# glowna.net
KiCad netlist of a schematic drawn in EAGLE
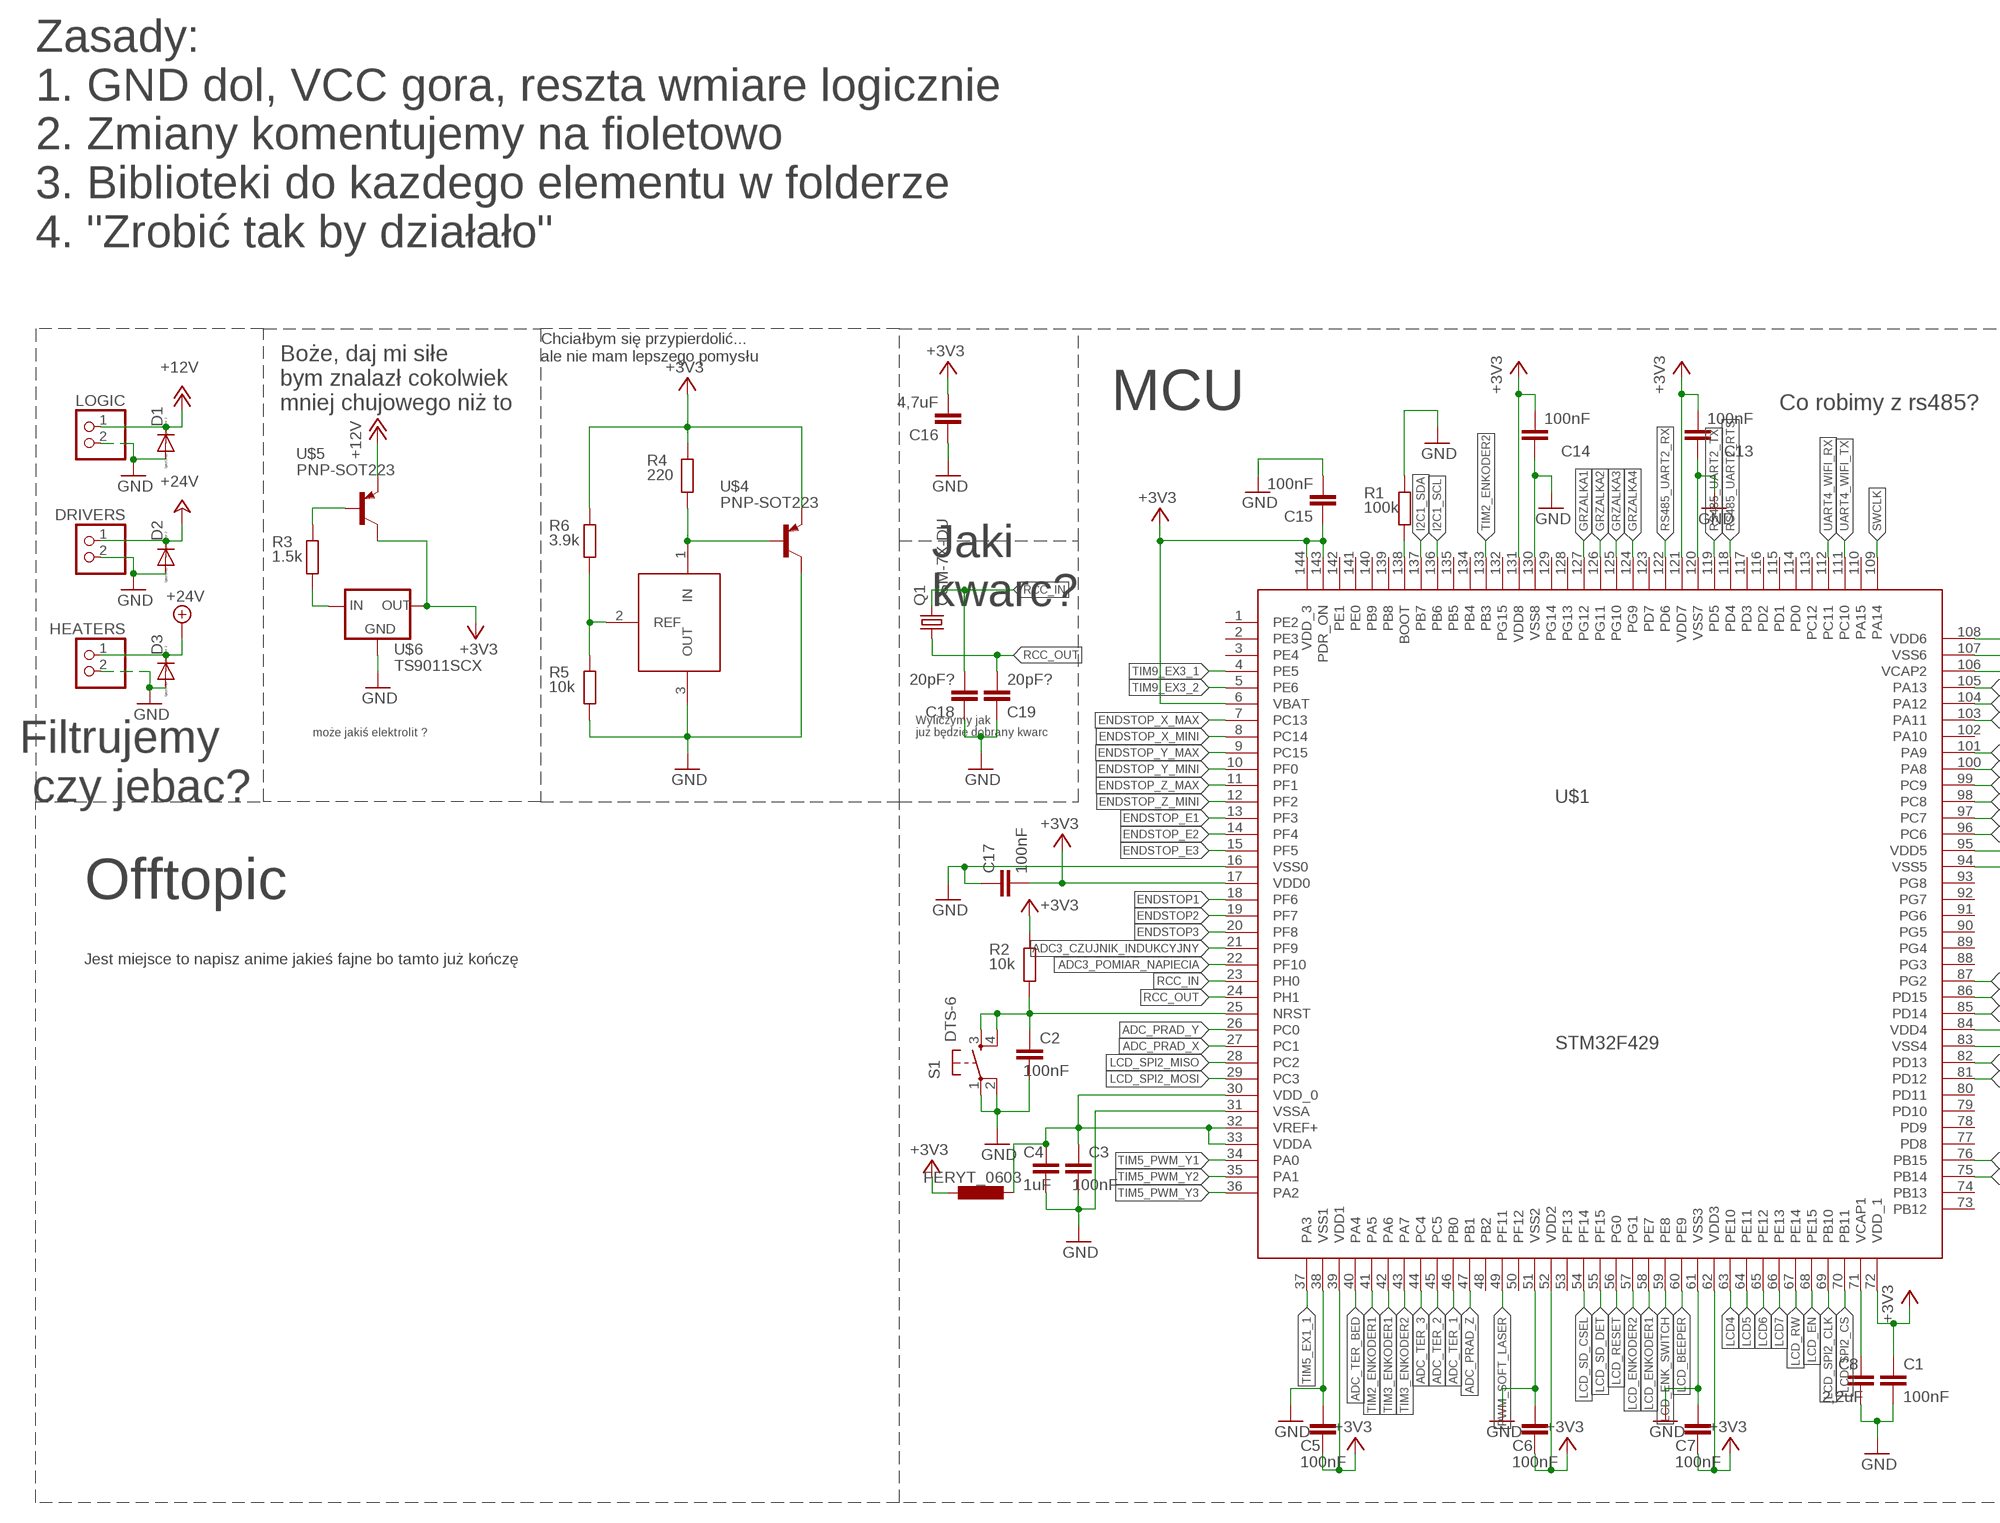
[diagram p0: schematic, sheet 1, part 1 of 2]
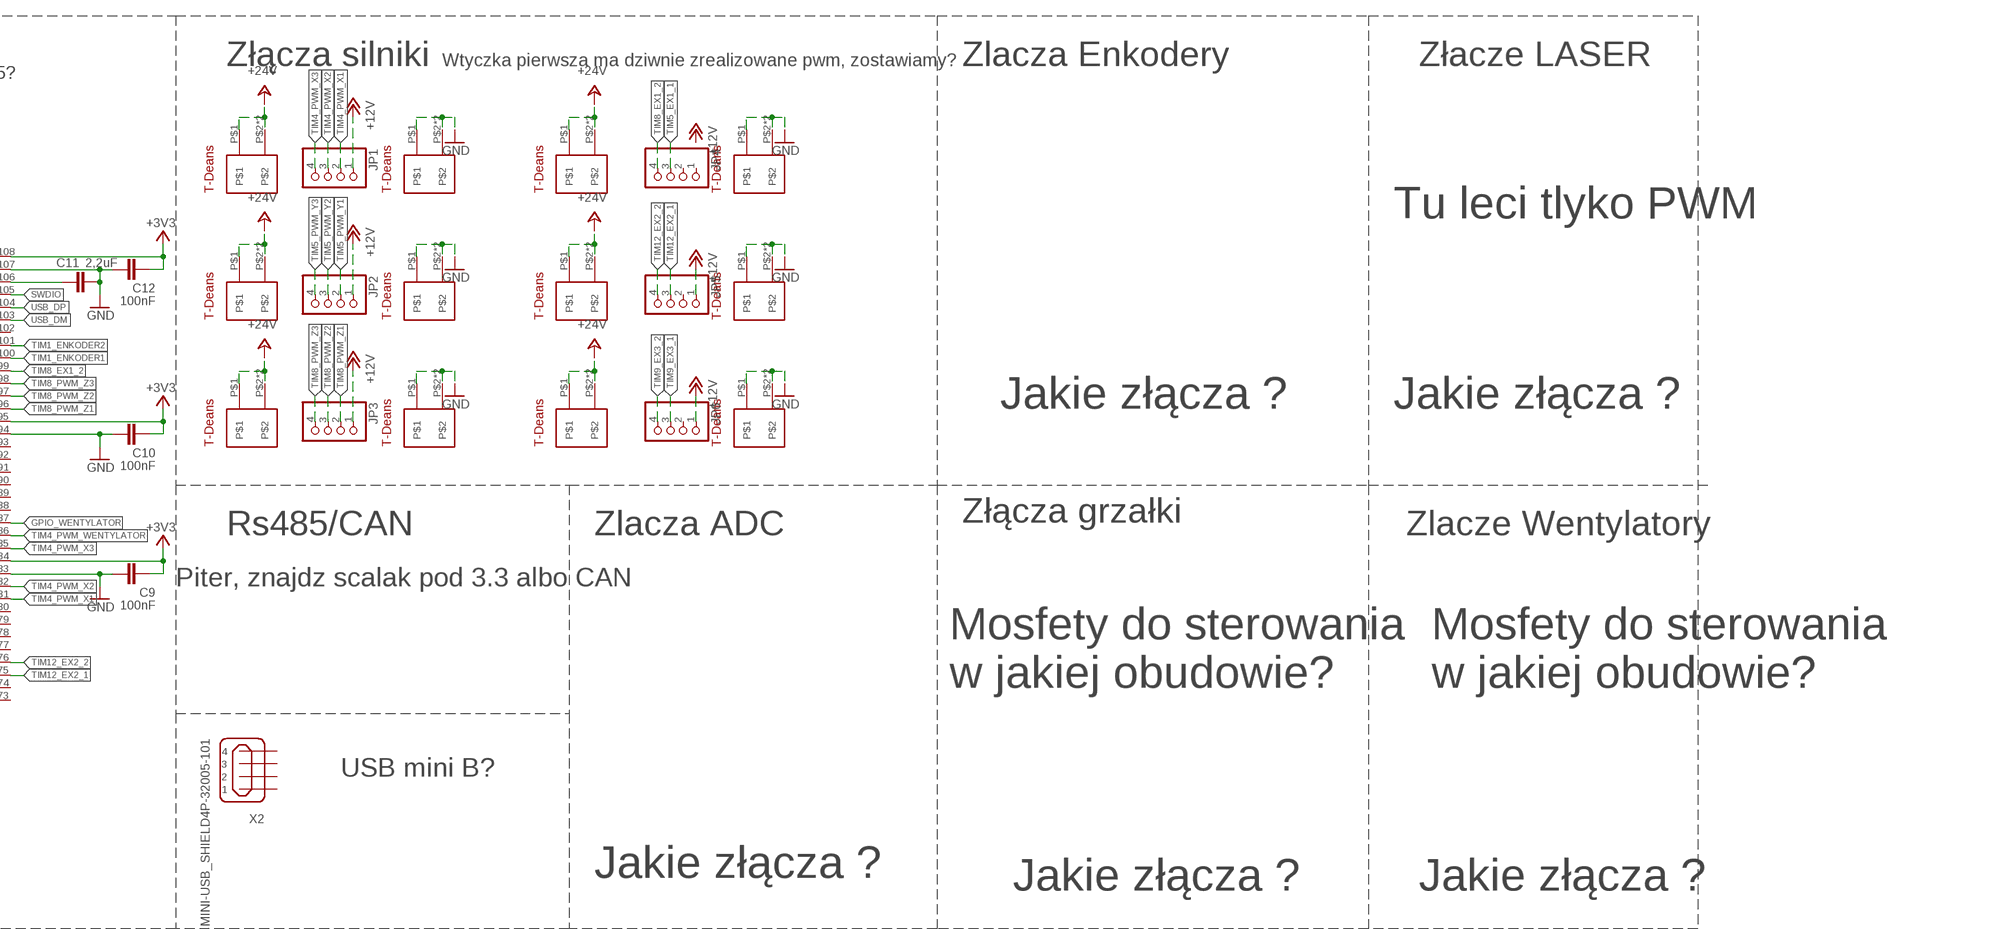
[diagram p1: schematic, sheet 1, part 2 of 2]

(export (version "E")
  (design (tool "Eeschema 10.0.6"))
  (components
    (comp (ref "C1")
      (value "100nF")
      (footprint "eagle-import:C0603")
      (libsource (lib "eagle-import") (part "C-EUC0603"))
    )
    (comp (ref "C2")
      (value "100nF")
      (footprint "eagle-import:C0603")
      (libsource (lib "eagle-import") (part "C-EUC0603"))
    )
    (comp (ref "C3")
      (value "100nF")
      (footprint "eagle-import:C0603")
      (libsource (lib "eagle-import") (part "C-EUC0603"))
    )
    (comp (ref "C4")
      (value "1uF")
      (footprint "eagle-import:C0603")
      (libsource (lib "eagle-import") (part "C-EUC0603"))
    )
    (comp (ref "C5")
      (value "100nF")
      (footprint "eagle-import:C0603")
      (libsource (lib "eagle-import") (part "C-EUC0603"))
    )
    (comp (ref "C6")
      (value "100nF")
      (footprint "eagle-import:C0603")
      (libsource (lib "eagle-import") (part "C-EUC0603"))
    )
    (comp (ref "C7")
      (value "100nF")
      (footprint "eagle-import:C0603")
      (libsource (lib "eagle-import") (part "C-EUC0603"))
    )
    (comp (ref "C8")
      (value "2,2uF")
      (footprint "eagle-import:C0603")
      (libsource (lib "eagle-import") (part "C-EUC0603"))
    )
    (comp (ref "C9")
      (value "100nF")
      (footprint "eagle-import:C0603")
      (libsource (lib "eagle-import") (part "C-EUC0603"))
    )
    (comp (ref "C10")
      (value "100nF")
      (footprint "eagle-import:C0603")
      (libsource (lib "eagle-import") (part "C-EUC0603"))
    )
    (comp (ref "C11")
      (value "2,2uF")
      (footprint "eagle-import:C0603")
      (libsource (lib "eagle-import") (part "C-EUC0603"))
    )
    (comp (ref "C12")
      (value "100nF")
      (footprint "eagle-import:C0603")
      (libsource (lib "eagle-import") (part "C-EUC0603"))
    )
    (comp (ref "C13")
      (value "100nF")
      (footprint "eagle-import:C0603")
      (libsource (lib "eagle-import") (part "C-EUC0603"))
    )
    (comp (ref "C14")
      (value "100nF")
      (footprint "eagle-import:C0603")
      (libsource (lib "eagle-import") (part "C-EUC0603"))
    )
    (comp (ref "C15")
      (value "100nF")
      (footprint "eagle-import:C0603")
      (libsource (lib "eagle-import") (part "C-EUC0603"))
    )
    (comp (ref "C16")
      (value "4,7uF")
      (footprint "eagle-import:C0603")
      (libsource (lib "eagle-import") (part "C-EUC0603"))
    )
    (comp (ref "C17")
      (value "100nF")
      (footprint "eagle-import:C0603")
      (libsource (lib "eagle-import") (part "C-EUC0603"))
    )
    (comp (ref "C18")
      (value "20pF?")
      (footprint "eagle-import:C0603")
      (libsource (lib "eagle-import") (part "C-EUC0603"))
    )
    (comp (ref "C19")
      (value "20pF?")
      (footprint "eagle-import:C0603")
      (libsource (lib "eagle-import") (part "C-EUC0603"))
    )
    (comp (ref "D1")
      (value "DIODE-DO-214AC")
      (footprint "eagle-import:DO-214AC")
      (libsource (lib "eagle-import") (part "DIODE-DO-214AC"))
    )
    (comp (ref "D2")
      (value "DIODE-DO-214AC")
      (footprint "eagle-import:DO-214AC")
      (libsource (lib "eagle-import") (part "DIODE-DO-214AC"))
    )
    (comp (ref "D3")
      (value "DIODE-DO-214AC")
      (footprint "eagle-import:DO-214AC")
      (libsource (lib "eagle-import") (part "DIODE-DO-214AC"))
    )
    (comp (ref "DRIVERS")
      (value "PINHD-1X2")
      (footprint "eagle-import:1X02")
      (libsource (lib "eagle-import") (part "PINHD-1X2"))
    )
    (comp (ref "HEATERS")
      (value "PINHD-1X2")
      (footprint "eagle-import:1X02")
      (libsource (lib "eagle-import") (part "PINHD-1X2"))
    )
    (comp (ref "JP1")
      (value "PINHD-1X4")
      (footprint "eagle-import:1X04")
      (libsource (lib "eagle-import") (part "PINHD-1X4"))
    )
    (comp (ref "JP2")
      (value "PINHD-1X4")
      (footprint "eagle-import:1X04")
      (libsource (lib "eagle-import") (part "PINHD-1X4"))
    )
    (comp (ref "JP3")
      (value "PINHD-1X4")
      (footprint "eagle-import:1X04")
      (libsource (lib "eagle-import") (part "PINHD-1X4"))
    )
    (comp (ref "JP4")
      (value "PINHD-1X4")
      (footprint "eagle-import:1X04")
      (libsource (lib "eagle-import") (part "PINHD-1X4"))
    )
    (comp (ref "JP5")
      (value "PINHD-1X4")
      (footprint "eagle-import:1X04")
      (libsource (lib "eagle-import") (part "PINHD-1X4"))
    )
    (comp (ref "JP6")
      (value "PINHD-1X4")
      (footprint "eagle-import:1X04")
      (libsource (lib "eagle-import") (part "PINHD-1X4"))
    )
    (comp (ref "LOGIC")
      (value "PINHD-1X2")
      (footprint "eagle-import:1X02")
      (libsource (lib "eagle-import") (part "PINHD-1X2"))
    )
    (comp (ref "Q1")
      (value "CSM-7X-DU")
      (footprint "eagle-import:CSM-7X-DU")
      (libsource (lib "eagle-import") (part "CSM-7X-DU"))
    )
    (comp (ref "R1")
      (value "100k")
      (footprint "eagle-import:R0603")
      (libsource (lib "eagle-import") (part "R-EU_R0603"))
    )
    (comp (ref "R2")
      (value "10k")
      (footprint "eagle-import:R0603")
      (libsource (lib "eagle-import") (part "R-EU_R0603"))
    )
    (comp (ref "R3")
      (value "1.5k")
      (footprint "eagle-import:R0603")
      (libsource (lib "eagle-import") (part "R-EU_R0603"))
    )
    (comp (ref "R4")
      (value "220")
      (footprint "eagle-import:R0603")
      (libsource (lib "eagle-import") (part "R-EU_R0603"))
    )
    (comp (ref "R5")
      (value "10k")
      (footprint "eagle-import:R0603")
      (libsource (lib "eagle-import") (part "R-EU_R0603"))
    )
    (comp (ref "R6")
      (value "3.9k")
      (footprint "eagle-import:R0603")
      (libsource (lib "eagle-import") (part "R-EU_R0603"))
    )
    (comp (ref "S1")
      (value "DTS-6")
      (footprint "eagle-import:DTS-6")
      (libsource (lib "eagle-import") (part "DTS-6"))
    )
    (comp (ref "U$1")
      (value "STM32F429")
      (footprint "eagle-import:SQFP-S-20X20-144")
      (libsource (lib "eagle-import") (part "STM32F429"))
    )
    (comp (ref "U$2")
      (value "FERYT_0603")
      (footprint "eagle-import:R0603")
      (libsource (lib "eagle-import") (part "FERYT_0603"))
    )
    (comp (ref "U$3")
      (value "TL431AIDBZR")
      (footprint "eagle-import:SOT23")
      (libsource (lib "eagle-import") (part "TL431AIDBZR"))
    )
    (comp (ref "U$4")
      (value "PNP-SOT223")
      (footprint "eagle-import:SOT223")
      (libsource (lib "eagle-import") (part "PNP-SOT223"))
    )
    (comp (ref "U$5")
      (value "PNP-SOT223")
      (footprint "eagle-import:SOT223")
      (libsource (lib "eagle-import") (part "PNP-SOT223"))
    )
    (comp (ref "U$6")
      (value "TS9011SCX")
      (footprint "eagle-import:SOT23")
      (libsource (lib "eagle-import") (part "TS9011SCX"))
    )
    (comp (ref "U$7")
      (value "T-DEANS")
      (footprint "eagle-import:T-DEANS")
      (libsource (lib "eagle-import") (part "T-DEANS"))
    )
    (comp (ref "U$8")
      (value "T-DEANS")
      (footprint "eagle-import:T-DEANS")
      (libsource (lib "eagle-import") (part "T-DEANS"))
    )
    (comp (ref "U$9")
      (value "T-DEANS")
      (footprint "eagle-import:T-DEANS")
      (libsource (lib "eagle-import") (part "T-DEANS"))
    )
    (comp (ref "U$10")
      (value "T-DEANS")
      (footprint "eagle-import:T-DEANS")
      (libsource (lib "eagle-import") (part "T-DEANS"))
    )
    (comp (ref "U$11")
      (value "T-DEANS")
      (footprint "eagle-import:T-DEANS")
      (libsource (lib "eagle-import") (part "T-DEANS"))
    )
    (comp (ref "U$12")
      (value "T-DEANS")
      (footprint "eagle-import:T-DEANS")
      (libsource (lib "eagle-import") (part "T-DEANS"))
    )
    (comp (ref "U$13")
      (value "T-DEANS")
      (footprint "eagle-import:T-DEANS")
      (libsource (lib "eagle-import") (part "T-DEANS"))
    )
    (comp (ref "U$14")
      (value "T-DEANS")
      (footprint "eagle-import:T-DEANS")
      (libsource (lib "eagle-import") (part "T-DEANS"))
    )
    (comp (ref "U$15")
      (value "T-DEANS")
      (footprint "eagle-import:T-DEANS")
      (libsource (lib "eagle-import") (part "T-DEANS"))
    )
    (comp (ref "U$16")
      (value "T-DEANS")
      (footprint "eagle-import:T-DEANS")
      (libsource (lib "eagle-import") (part "T-DEANS"))
    )
    (comp (ref "U$17")
      (value "T-DEANS")
      (footprint "eagle-import:T-DEANS")
      (libsource (lib "eagle-import") (part "T-DEANS"))
    )
    (comp (ref "U$18")
      (value "T-DEANS")
      (footprint "eagle-import:T-DEANS")
      (libsource (lib "eagle-import") (part "T-DEANS"))
    )
    (comp (ref "X2")
      (value "MINI-USB_SHIELD4P-32005-101")
      (footprint "eagle-import:32005-101")
      (libsource (lib "eagle-import") (part "MINI-USB_SHIELD4P-32005-101"))
    )
  )
  (nets
    (net (code "1") (name "+3V3") (class "Default")
      (node (ref "C1") (pin "1") (pinfunction "1_1") (pintype "passive"))
      (node (ref "C10") (pin "2") (pinfunction "2_2") (pintype "passive"))
      (node (ref "C12") (pin "2") (pinfunction "2_2") (pintype "passive"))
      (node (ref "C13") (pin "2") (pinfunction "2_2") (pintype "passive"))
      (node (ref "C14") (pin "2") (pinfunction "2_2") (pintype "passive"))
      (node (ref "C15") (pin "1") (pinfunction "1_1") (pintype "passive"))
      (node (ref "C16") (pin "2") (pinfunction "2_2") (pintype "passive"))
      (node (ref "C17") (pin "2") (pinfunction "2_2") (pintype "passive"))
      (node (ref "C5") (pin "2") (pinfunction "2_2") (pintype "passive"))
      (node (ref "C6") (pin "2") (pinfunction "2_2") (pintype "passive"))
      (node (ref "C7") (pin "2") (pinfunction "2_2") (pintype "passive"))
      (node (ref "C9") (pin "2") (pinfunction "2_2") (pintype "passive"))
      (node (ref "R2") (pin "1") (pinfunction "1_1") (pintype "passive"))
      (node (ref "R4") (pin "1") (pinfunction "1_1") (pintype "passive"))
      (node (ref "R6") (pin "1") (pinfunction "1_1") (pintype "passive"))
      (node (ref "U$1") (pin "108") (pinfunction "VDD6_108") (pintype "bidirectional"))
      (node (ref "U$1") (pin "121") (pinfunction "VDD7_121") (pintype "bidirectional"))
      (node (ref "U$1") (pin "131") (pinfunction "VDD8_131") (pintype "bidirectional"))
      (node (ref "U$1") (pin "143") (pinfunction "PDR_ON_143") (pintype "bidirectional"))
      (node (ref "U$1") (pin "144") (pinfunction "VDD_3_144") (pintype "bidirectional"))
      (node (ref "U$1") (pin "17") (pinfunction "VDD0_17") (pintype "bidirectional"))
      (node (ref "U$1") (pin "39") (pinfunction "VDD1_39") (pintype "bidirectional"))
      (node (ref "U$1") (pin "52") (pinfunction "VDD2_52") (pintype "bidirectional"))
      (node (ref "U$1") (pin "6") (pinfunction "VBAT_6") (pintype "bidirectional"))
      (node (ref "U$1") (pin "62") (pinfunction "VDD3_62") (pintype "bidirectional"))
      (node (ref "U$1") (pin "72") (pinfunction "VDD_1_72") (pintype "bidirectional"))
      (node (ref "U$1") (pin "84") (pinfunction "VDD4_84") (pintype "bidirectional"))
      (node (ref "U$1") (pin "95") (pinfunction "VDD5_95") (pintype "bidirectional"))
      (node (ref "U$2") (pin "1") (pinfunction "1_1") (pintype "passive"))
      (node (ref "U$4") (pin "3") (pinfunction "E_3") (pintype "passive"))
      (node (ref "U$5") (pin "2") (pinfunction "C_2") (pintype "passive"))
      (node (ref "U$5") (pin "4") (pinfunction "C_4") (pintype "passive"))
      (node (ref "U$6") (pin "2") (pinfunction "OUT_2") (pintype "passive"))
    )
    (net (code "2") (name "+12V") (class "Default")
      (node (ref "D1") (pin "C") (pinfunction "C_C") (pintype "passive"))
      (node (ref "JP1") (pin "1") (pinfunction "1_1") (pintype "passive"))
      (node (ref "JP2") (pin "1") (pinfunction "1_1") (pintype "passive"))
      (node (ref "JP3") (pin "1") (pinfunction "1_1") (pintype "passive"))
      (node (ref "JP5") (pin "1") (pinfunction "1_1") (pintype "passive"))
      (node (ref "JP6") (pin "1") (pinfunction "1_1") (pintype "passive"))
      (node (ref "LOGIC") (pin "1") (pinfunction "1_1") (pintype "passive"))
      (node (ref "U$5") (pin "3") (pinfunction "E_3") (pintype "passive"))
    )
    (net (code "3") (name "+24V") (class "Default")
      (node (ref "D2") (pin "C") (pinfunction "C_C") (pintype "passive"))
      (node (ref "D3") (pin "C") (pinfunction "C_C") (pintype "passive"))
      (node (ref "DRIVERS") (pin "1") (pinfunction "1_1") (pintype "passive"))
      (node (ref "HEATERS") (pin "1") (pinfunction "1_1") (pintype "passive"))
      (node (ref "U$11") (pin "P$1") (pinfunction "P$1_P$1") (pintype "bidirectional"))
      (node (ref "U$11") (pin "P$2") (pinfunction "P$2_P$2") (pintype "bidirectional"))
      (node (ref "U$11") (pin "P$3") (pinfunction "P$2_P$3") (pintype "bidirectional"))
      (node (ref "U$13") (pin "P$1") (pinfunction "P$1_P$1") (pintype "bidirectional"))
      (node (ref "U$13") (pin "P$2") (pinfunction "P$2_P$2") (pintype "bidirectional"))
      (node (ref "U$13") (pin "P$3") (pinfunction "P$2_P$3") (pintype "bidirectional"))
      (node (ref "U$15") (pin "P$1") (pinfunction "P$1_P$1") (pintype "bidirectional"))
      (node (ref "U$15") (pin "P$2") (pinfunction "P$2_P$2") (pintype "bidirectional"))
      (node (ref "U$15") (pin "P$3") (pinfunction "P$2_P$3") (pintype "bidirectional"))
      (node (ref "U$17") (pin "P$1") (pinfunction "P$1_P$1") (pintype "bidirectional"))
      (node (ref "U$17") (pin "P$2") (pinfunction "P$2_P$2") (pintype "bidirectional"))
      (node (ref "U$17") (pin "P$3") (pinfunction "P$2_P$3") (pintype "bidirectional"))
      (node (ref "U$7") (pin "P$1") (pinfunction "P$1_P$1") (pintype "bidirectional"))
      (node (ref "U$7") (pin "P$2") (pinfunction "P$2_P$2") (pintype "bidirectional"))
      (node (ref "U$7") (pin "P$3") (pinfunction "P$2_P$3") (pintype "bidirectional"))
      (node (ref "U$9") (pin "P$1") (pinfunction "P$1_P$1") (pintype "bidirectional"))
      (node (ref "U$9") (pin "P$2") (pinfunction "P$2_P$2") (pintype "bidirectional"))
      (node (ref "U$9") (pin "P$3") (pinfunction "P$2_P$3") (pintype "bidirectional"))
    )
    (net (code "4") (name "ADC3_CZUJNIK_INDUKCYJNY") (class "Default")
      (node (ref "U$1") (pin "21") (pinfunction "PF9_21") (pintype "bidirectional"))
    )
    (net (code "5") (name "ADC3_POMIAR_NAPIECIA") (class "Default")
      (node (ref "U$1") (pin "22") (pinfunction "PF10_22") (pintype "bidirectional"))
    )
    (net (code "6") (name "ADC_PRAD_X") (class "Default")
      (node (ref "U$1") (pin "27") (pinfunction "PC1_27") (pintype "bidirectional"))
    )
    (net (code "7") (name "ADC_PRAD_Y") (class "Default")
      (node (ref "U$1") (pin "26") (pinfunction "PC0_26") (pintype "bidirectional"))
    )
    (net (code "8") (name "ADC_PRAD_Z") (class "Default")
      (node (ref "U$1") (pin "47") (pinfunction "PB1_47") (pintype "bidirectional"))
    )
    (net (code "9") (name "ADC_TER_1") (class "Default")
      (node (ref "U$1") (pin "46") (pinfunction "PB0_46") (pintype "bidirectional"))
    )
    (net (code "10") (name "ADC_TER_2") (class "Default")
      (node (ref "U$1") (pin "45") (pinfunction "PC5_45") (pintype "bidirectional"))
    )
    (net (code "11") (name "ADC_TER_3") (class "Default")
      (node (ref "U$1") (pin "44") (pinfunction "PC4_44") (pintype "bidirectional"))
    )
    (net (code "12") (name "ADC_TER_BED") (class "Default")
      (node (ref "U$1") (pin "40") (pinfunction "PA4_40") (pintype "bidirectional"))
    )
    (net (code "13") (name "ENDSTOP1") (class "Default")
      (node (ref "U$1") (pin "18") (pinfunction "PF6_18") (pintype "bidirectional"))
    )
    (net (code "14") (name "ENDSTOP2") (class "Default")
      (node (ref "U$1") (pin "19") (pinfunction "PF7_19") (pintype "bidirectional"))
    )
    (net (code "15") (name "ENDSTOP3") (class "Default")
      (node (ref "U$1") (pin "20") (pinfunction "PF8_20") (pintype "bidirectional"))
    )
    (net (code "16") (name "ENDSTOP_E1") (class "Default")
      (node (ref "U$1") (pin "13") (pinfunction "PF3_13") (pintype "bidirectional"))
    )
    (net (code "17") (name "ENDSTOP_E2") (class "Default")
      (node (ref "U$1") (pin "14") (pinfunction "PF4_14") (pintype "bidirectional"))
    )
    (net (code "18") (name "ENDSTOP_E3") (class "Default")
      (node (ref "U$1") (pin "15") (pinfunction "PF5_15") (pintype "bidirectional"))
    )
    (net (code "19") (name "ENDSTOP_X_MAX") (class "Default")
      (node (ref "U$1") (pin "7") (pinfunction "PC13_7") (pintype "bidirectional"))
    )
    (net (code "20") (name "ENDSTOP_X_MINI") (class "Default")
      (node (ref "U$1") (pin "8") (pinfunction "PC14_8") (pintype "bidirectional"))
    )
    (net (code "21") (name "ENDSTOP_Y_MAX") (class "Default")
      (node (ref "U$1") (pin "9") (pinfunction "PC15_9") (pintype "bidirectional"))
    )
    (net (code "22") (name "ENDSTOP_Y_MINI") (class "Default")
      (node (ref "U$1") (pin "10") (pinfunction "PF0_10") (pintype "bidirectional"))
    )
    (net (code "23") (name "ENDSTOP_Z_MAX") (class "Default")
      (node (ref "U$1") (pin "11") (pinfunction "PF1_11") (pintype "bidirectional"))
    )
    (net (code "24") (name "ENDSTOP_Z_MINI") (class "Default")
      (node (ref "U$1") (pin "12") (pinfunction "PF2_12") (pintype "bidirectional"))
    )
    (net (code "25") (name "GND") (class "Default")
      (node (ref "C1") (pin "2") (pinfunction "2_2") (pintype "passive"))
      (node (ref "C10") (pin "1") (pinfunction "1_1") (pintype "passive"))
      (node (ref "C11") (pin "2") (pinfunction "2_2") (pintype "passive"))
      (node (ref "C12") (pin "1") (pinfunction "1_1") (pintype "passive"))
      (node (ref "C13") (pin "1") (pinfunction "1_1") (pintype "passive"))
      (node (ref "C14") (pin "1") (pinfunction "1_1") (pintype "passive"))
      (node (ref "C15") (pin "2") (pinfunction "2_2") (pintype "passive"))
      (node (ref "C16") (pin "1") (pinfunction "1_1") (pintype "passive"))
      (node (ref "C17") (pin "1") (pinfunction "1_1") (pintype "passive"))
      (node (ref "C18") (pin "1") (pinfunction "1_1") (pintype "passive"))
      (node (ref "C19") (pin "1") (pinfunction "1_1") (pintype "passive"))
      (node (ref "C2") (pin "2") (pinfunction "2_2") (pintype "passive"))
      (node (ref "C3") (pin "2") (pinfunction "2_2") (pintype "passive"))
      (node (ref "C4") (pin "2") (pinfunction "2_2") (pintype "passive"))
      (node (ref "C5") (pin "1") (pinfunction "1_1") (pintype "passive"))
      (node (ref "C6") (pin "1") (pinfunction "1_1") (pintype "passive"))
      (node (ref "C7") (pin "1") (pinfunction "1_1") (pintype "passive"))
      (node (ref "C8") (pin "2") (pinfunction "2_2") (pintype "passive"))
      (node (ref "C9") (pin "1") (pinfunction "1_1") (pintype "passive"))
      (node (ref "D1") (pin "A") (pinfunction "A_A") (pintype "passive"))
      (node (ref "D2") (pin "A") (pinfunction "A_A") (pintype "passive"))
      (node (ref "D3") (pin "A") (pinfunction "A_A") (pintype "passive"))
      (node (ref "DRIVERS") (pin "2") (pinfunction "2_2") (pintype "passive"))
      (node (ref "HEATERS") (pin "2") (pinfunction "2_2") (pintype "passive"))
      (node (ref "LOGIC") (pin "2") (pinfunction "2_2") (pintype "passive"))
      (node (ref "R1") (pin "1") (pinfunction "1_1") (pintype "passive"))
      (node (ref "R5") (pin "2") (pinfunction "2_2") (pintype "passive"))
      (node (ref "S1") (pin "1") (pinfunction "1_1") (pintype "passive"))
      (node (ref "S1") (pin "2") (pinfunction "2_2") (pintype "passive"))
      (node (ref "U$1") (pin "107") (pinfunction "VSS6_107") (pintype "bidirectional"))
      (node (ref "U$1") (pin "120") (pinfunction "VSS7_120") (pintype "bidirectional"))
      (node (ref "U$1") (pin "130") (pinfunction "VSS8_130") (pintype "bidirectional"))
      (node (ref "U$1") (pin "16") (pinfunction "VSS0_16") (pintype "bidirectional"))
      (node (ref "U$1") (pin "31") (pinfunction "VSSA_31") (pintype "bidirectional"))
      (node (ref "U$1") (pin "38") (pinfunction "VSS1_38") (pintype "bidirectional"))
      (node (ref "U$1") (pin "51") (pinfunction "VSS2_51") (pintype "bidirectional"))
      (node (ref "U$1") (pin "61") (pinfunction "VSS3_61") (pintype "bidirectional"))
      (node (ref "U$1") (pin "83") (pinfunction "VSS4_83") (pintype "bidirectional"))
      (node (ref "U$1") (pin "94") (pinfunction "VSS5_94") (pintype "bidirectional"))
      (node (ref "U$10") (pin "P$1") (pinfunction "P$1_P$1") (pintype "bidirectional"))
      (node (ref "U$10") (pin "P$2") (pinfunction "P$2_P$2") (pintype "bidirectional"))
      (node (ref "U$10") (pin "P$3") (pinfunction "P$2_P$3") (pintype "bidirectional"))
      (node (ref "U$12") (pin "P$1") (pinfunction "P$1_P$1") (pintype "bidirectional"))
      (node (ref "U$12") (pin "P$2") (pinfunction "P$2_P$2") (pintype "bidirectional"))
      (node (ref "U$12") (pin "P$3") (pinfunction "P$2_P$3") (pintype "bidirectional"))
      (node (ref "U$14") (pin "P$1") (pinfunction "P$1_P$1") (pintype "bidirectional"))
      (node (ref "U$14") (pin "P$2") (pinfunction "P$2_P$2") (pintype "bidirectional"))
      (node (ref "U$14") (pin "P$3") (pinfunction "P$2_P$3") (pintype "bidirectional"))
      (node (ref "U$16") (pin "P$1") (pinfunction "P$1_P$1") (pintype "bidirectional"))
      (node (ref "U$16") (pin "P$2") (pinfunction "P$2_P$2") (pintype "bidirectional"))
      (node (ref "U$16") (pin "P$3") (pinfunction "P$2_P$3") (pintype "bidirectional"))
      (node (ref "U$18") (pin "P$1") (pinfunction "P$1_P$1") (pintype "bidirectional"))
      (node (ref "U$18") (pin "P$2") (pinfunction "P$2_P$2") (pintype "bidirectional"))
      (node (ref "U$18") (pin "P$3") (pinfunction "P$2_P$3") (pintype "bidirectional"))
      (node (ref "U$3") (pin "3") (pinfunction "OUT_3") (pintype "bidirectional"))
      (node (ref "U$4") (pin "2") (pinfunction "C_2") (pintype "passive"))
      (node (ref "U$4") (pin "4") (pinfunction "C_4") (pintype "passive"))
      (node (ref "U$6") (pin "1") (pinfunction "GND_1") (pintype "input"))
      (node (ref "U$8") (pin "P$1") (pinfunction "P$1_P$1") (pintype "bidirectional"))
      (node (ref "U$8") (pin "P$2") (pinfunction "P$2_P$2") (pintype "bidirectional"))
      (node (ref "U$8") (pin "P$3") (pinfunction "P$2_P$3") (pintype "bidirectional"))
    )
    (net (code "26") (name "GPIO_WENTYLATOR") (class "Default")
      (node (ref "U$1") (pin "87") (pinfunction "PG2_87") (pintype "bidirectional"))
    )
    (net (code "27") (name "GRZALKA1") (class "Default")
      (node (ref "U$1") (pin "127") (pinfunction "PG12_127") (pintype "bidirectional"))
    )
    (net (code "28") (name "GRZALKA2") (class "Default")
      (node (ref "U$1") (pin "126") (pinfunction "PG11_126") (pintype "bidirectional"))
    )
    (net (code "29") (name "GRZALKA3") (class "Default")
      (node (ref "U$1") (pin "125") (pinfunction "PG10_125") (pintype "bidirectional"))
    )
    (net (code "30") (name "GRZALKA4") (class "Default")
      (node (ref "U$1") (pin "124") (pinfunction "PG9_124") (pintype "bidirectional"))
    )
    (net (code "31") (name "I2C1_SCL") (class "Default")
      (node (ref "U$1") (pin "136") (pinfunction "PB6_136") (pintype "bidirectional"))
    )
    (net (code "32") (name "I2C1_SDA") (class "Default")
      (node (ref "U$1") (pin "137") (pinfunction "PB7_137") (pintype "bidirectional"))
    )
    (net (code "33") (name "LCD4") (class "Default")
      (node (ref "U$1") (pin "63") (pinfunction "PE10_63") (pintype "bidirectional"))
    )
    (net (code "34") (name "LCD5") (class "Default")
      (node (ref "U$1") (pin "64") (pinfunction "PE11_64") (pintype "bidirectional"))
    )
    (net (code "35") (name "LCD6") (class "Default")
      (node (ref "U$1") (pin "65") (pinfunction "PE12_65") (pintype "bidirectional"))
    )
    (net (code "36") (name "LCD7") (class "Default")
      (node (ref "U$1") (pin "66") (pinfunction "PE13_66") (pintype "bidirectional"))
    )
    (net (code "37") (name "LCD_BEEPER") (class "Default")
      (node (ref "U$1") (pin "60") (pinfunction "PE9_60") (pintype "bidirectional"))
    )
    (net (code "38") (name "LCD_EN") (class "Default")
      (node (ref "U$1") (pin "68") (pinfunction "PE15_68") (pintype "bidirectional"))
    )
    (net (code "39") (name "LCD_ENKODER1") (class "Default")
      (node (ref "U$1") (pin "58") (pinfunction "PE7_58") (pintype "bidirectional"))
    )
    (net (code "40") (name "LCD_ENKODER2") (class "Default")
      (node (ref "U$1") (pin "57") (pinfunction "PG1_57") (pintype "bidirectional"))
    )
    (net (code "41") (name "LCD_ENK_SWITCH") (class "Default")
      (node (ref "U$1") (pin "59") (pinfunction "PE8_59") (pintype "bidirectional"))
    )
    (net (code "42") (name "LCD_RESET") (class "Default")
      (node (ref "U$1") (pin "56") (pinfunction "PG0_56") (pintype "bidirectional"))
    )
    (net (code "43") (name "LCD_RW") (class "Default")
      (node (ref "U$1") (pin "67") (pinfunction "PE14_67") (pintype "bidirectional"))
    )
    (net (code "44") (name "LCD_SD_CSEL") (class "Default")
      (node (ref "U$1") (pin "54") (pinfunction "PF14_54") (pintype "bidirectional"))
    )
    (net (code "45") (name "LCD_SD_DET") (class "Default")
      (node (ref "U$1") (pin "55") (pinfunction "PF15_55") (pintype "bidirectional"))
    )
    (net (code "46") (name "LCD_SPI2_CLK") (class "Default")
      (node (ref "U$1") (pin "69") (pinfunction "PB10_69") (pintype "bidirectional"))
    )
    (net (code "47") (name "LCD_SPI2_CS") (class "Default")
      (node (ref "U$1") (pin "70") (pinfunction "PB11_70") (pintype "bidirectional"))
    )
    (net (code "48") (name "LCD_SPI2_MISO") (class "Default")
      (node (ref "U$1") (pin "28") (pinfunction "PC2_28") (pintype "bidirectional"))
    )
    (net (code "49") (name "LCD_SPI2_MOSI") (class "Default")
      (node (ref "U$1") (pin "29") (pinfunction "PC3_29") (pintype "bidirectional"))
    )
    (net (code "50") (name "Net-(U$1-BOOT)") (class "Default")
      (node (ref "R1") (pin "2") (pinfunction "2_2") (pintype "passive"))
      (node (ref "U$1") (pin "138") (pinfunction "BOOT_138") (pintype "bidirectional"))
    )
    (net (code "51") (name "Net-(U$1-NRST)") (class "Default")
      (node (ref "C2") (pin "1") (pinfunction "1_1") (pintype "passive"))
      (node (ref "R2") (pin "2") (pinfunction "2_2") (pintype "passive"))
      (node (ref "S1") (pin "3") (pinfunction "3_3") (pintype "passive"))
      (node (ref "S1") (pin "4") (pinfunction "4_4") (pintype "passive"))
      (node (ref "U$1") (pin "25") (pinfunction "NRST_25") (pintype "bidirectional"))
    )
    (net (code "52") (name "Net-(U$1-VCAP1)") (class "Default")
      (node (ref "C8") (pin "1") (pinfunction "1_1") (pintype "passive"))
      (node (ref "U$1") (pin "71") (pinfunction "VCAP1_71") (pintype "bidirectional"))
    )
    (net (code "53") (name "Net-(U$1-VCAP2)") (class "Default")
      (node (ref "C11") (pin "1") (pinfunction "1_1") (pintype "passive"))
      (node (ref "U$1") (pin "106") (pinfunction "VCAP2_106") (pintype "bidirectional"))
    )
    (net (code "54") (name "Net-(U$1-VDDA)") (class "Default")
      (node (ref "C3") (pin "1") (pinfunction "1_1") (pintype "passive"))
      (node (ref "C4") (pin "1") (pinfunction "1_1") (pintype "passive"))
      (node (ref "U$1") (pin "30") (pinfunction "VDD_0_30") (pintype "bidirectional"))
      (node (ref "U$1") (pin "32") (pinfunction "VREF+_32") (pintype "bidirectional"))
      (node (ref "U$1") (pin "33") (pinfunction "VDDA_33") (pintype "bidirectional"))
      (node (ref "U$2") (pin "2") (pinfunction "2_2") (pintype "passive"))
    )
    (net (code "55") (name "Net-(U$3-IN)") (class "Default")
      (node (ref "R4") (pin "2") (pinfunction "2_2") (pintype "passive"))
      (node (ref "U$3") (pin "1") (pinfunction "IN_1") (pintype "passive"))
      (node (ref "U$4") (pin "1") (pinfunction "B_1") (pintype "passive"))
    )
    (net (code "56") (name "Net-(U$3-REF)") (class "Default")
      (node (ref "R5") (pin "1") (pinfunction "1_1") (pintype "passive"))
      (node (ref "R6") (pin "2") (pinfunction "2_2") (pintype "passive"))
      (node (ref "U$3") (pin "2") (pinfunction "REF_2") (pintype "bidirectional"))
    )
    (net (code "57") (name "Net-(U$5-B)") (class "Default")
      (node (ref "R3") (pin "1") (pinfunction "1_1") (pintype "passive"))
      (node (ref "U$5") (pin "1") (pinfunction "B_1") (pintype "passive"))
    )
    (net (code "58") (name "Net-(U$6-IN)") (class "Default")
      (node (ref "R3") (pin "2") (pinfunction "2_2") (pintype "passive"))
      (node (ref "U$6") (pin "3") (pinfunction "IN_3") (pintype "input"))
    )
    (net (code "59") (name "PWM_SOFT_LASER") (class "Default")
      (node (ref "U$1") (pin "49") (pinfunction "PF11_49") (pintype "bidirectional"))
    )
    (net (code "60") (name "RCC_IN") (class "Default")
      (node (ref "C18") (pin "2") (pinfunction "2_2") (pintype "passive"))
      (node (ref "Q1") (pin "2") (pinfunction "2_2") (pintype "passive"))
      (node (ref "U$1") (pin "23") (pinfunction "PH0_23") (pintype "bidirectional"))
    )
    (net (code "61") (name "RCC_OUT") (class "Default")
      (node (ref "C19") (pin "2") (pinfunction "2_2") (pintype "passive"))
      (node (ref "Q1") (pin "1") (pinfunction "1_1") (pintype "passive"))
      (node (ref "U$1") (pin "24") (pinfunction "PH1_24") (pintype "bidirectional"))
    )
    (net (code "62") (name "RS485_UART2_RTS") (class "Default")
      (node (ref "U$1") (pin "118") (pinfunction "PD4_118") (pintype "bidirectional"))
    )
    (net (code "63") (name "RS485_UART2_RX") (class "Default")
      (node (ref "U$1") (pin "122") (pinfunction "PD6_122") (pintype "bidirectional"))
    )
    (net (code "64") (name "RS485_UART2_TX") (class "Default")
      (node (ref "U$1") (pin "119") (pinfunction "PD5_119") (pintype "bidirectional"))
    )
    (net (code "65") (name "SWCLK") (class "Default")
      (node (ref "U$1") (pin "109") (pinfunction "PA14_109") (pintype "bidirectional"))
    )
    (net (code "66") (name "SWDIO") (class "Default")
      (node (ref "U$1") (pin "105") (pinfunction "PA13_105") (pintype "bidirectional"))
    )
    (net (code "67") (name "TIM1_ENKODER1") (class "Default")
      (node (ref "U$1") (pin "100") (pinfunction "PA8_100") (pintype "bidirectional"))
    )
    (net (code "68") (name "TIM1_ENKODER2") (class "Default")
      (node (ref "U$1") (pin "101") (pinfunction "PA9_101") (pintype "bidirectional"))
    )
    (net (code "69") (name "TIM2_ENKODER1") (class "Default")
      (node (ref "U$1") (pin "41") (pinfunction "PA5_41") (pintype "bidirectional"))
    )
    (net (code "70") (name "TIM2_ENKODER2") (class "Default")
      (node (ref "U$1") (pin "133") (pinfunction "PB3_133") (pintype "bidirectional"))
    )
    (net (code "71") (name "TIM3_ENKODER1") (class "Default")
      (node (ref "U$1") (pin "42") (pinfunction "PA6_42") (pintype "bidirectional"))
    )
    (net (code "72") (name "TIM3_ENKODER2") (class "Default")
      (node (ref "U$1") (pin "43") (pinfunction "PA7_43") (pintype "bidirectional"))
    )
    (net (code "73") (name "TIM4_PWM_WENTYLATOR") (class "Default")
      (node (ref "U$1") (pin "86") (pinfunction "PD15_86") (pintype "bidirectional"))
    )
    (net (code "74") (name "TIM4_PWM_X1") (class "Default")
      (node (ref "JP1") (pin "2") (pinfunction "2_2") (pintype "passive"))
      (node (ref "U$1") (pin "81") (pinfunction "PD12_81") (pintype "bidirectional"))
    )
    (net (code "75") (name "TIM4_PWM_X2") (class "Default")
      (node (ref "JP1") (pin "3") (pinfunction "3_3") (pintype "passive"))
      (node (ref "U$1") (pin "82") (pinfunction "PD13_82") (pintype "bidirectional"))
    )
    (net (code "76") (name "TIM4_PWM_X3") (class "Default")
      (node (ref "JP1") (pin "4") (pinfunction "4_4") (pintype "passive"))
      (node (ref "U$1") (pin "85") (pinfunction "PD14_85") (pintype "bidirectional"))
    )
    (net (code "77") (name "TIM5_EX1_1") (class "Default")
      (node (ref "JP4") (pin "3") (pinfunction "3_3") (pintype "passive"))
      (node (ref "U$1") (pin "37") (pinfunction "PA3_37") (pintype "bidirectional"))
    )
    (net (code "78") (name "TIM5_PWM_Y1") (class "Default")
      (node (ref "JP2") (pin "2") (pinfunction "2_2") (pintype "passive"))
      (node (ref "U$1") (pin "34") (pinfunction "PA0_34") (pintype "bidirectional"))
    )
    (net (code "79") (name "TIM5_PWM_Y2") (class "Default")
      (node (ref "JP2") (pin "3") (pinfunction "3_3") (pintype "passive"))
      (node (ref "U$1") (pin "35") (pinfunction "PA1_35") (pintype "bidirectional"))
    )
    (net (code "80") (name "TIM5_PWM_Y3") (class "Default")
      (node (ref "JP2") (pin "4") (pinfunction "4_4") (pintype "passive"))
      (node (ref "U$1") (pin "36") (pinfunction "PA2_36") (pintype "bidirectional"))
    )
    (net (code "81") (name "TIM8_EX1_2") (class "Default")
      (node (ref "JP4") (pin "4") (pinfunction "4_4") (pintype "passive"))
      (node (ref "U$1") (pin "99") (pinfunction "PC9_99") (pintype "bidirectional"))
    )
    (net (code "82") (name "TIM8_PWM_Z1") (class "Default")
      (node (ref "JP3") (pin "2") (pinfunction "2_2") (pintype "passive"))
      (node (ref "U$1") (pin "96") (pinfunction "PC6_96") (pintype "bidirectional"))
    )
    (net (code "83") (name "TIM8_PWM_Z2") (class "Default")
      (node (ref "JP3") (pin "3") (pinfunction "3_3") (pintype "passive"))
      (node (ref "U$1") (pin "97") (pinfunction "PC7_97") (pintype "bidirectional"))
    )
    (net (code "84") (name "TIM8_PWM_Z3") (class "Default")
      (node (ref "JP3") (pin "4") (pinfunction "4_4") (pintype "passive"))
      (node (ref "U$1") (pin "98") (pinfunction "PC8_98") (pintype "bidirectional"))
    )
    (net (code "85") (name "TIM9_EX3_1") (class "Default")
      (node (ref "JP6") (pin "3") (pinfunction "3_3") (pintype "passive"))
      (node (ref "U$1") (pin "4") (pinfunction "PE5_4") (pintype "bidirectional"))
    )
    (net (code "86") (name "TIM9_EX3_2") (class "Default")
      (node (ref "JP6") (pin "4") (pinfunction "4_4") (pintype "passive"))
      (node (ref "U$1") (pin "5") (pinfunction "PE6_5") (pintype "bidirectional"))
    )
    (net (code "87") (name "TIM12_EX2_1") (class "Default")
      (node (ref "JP5") (pin "3") (pinfunction "3_3") (pintype "passive"))
      (node (ref "U$1") (pin "75") (pinfunction "PB14_75") (pintype "bidirectional"))
    )
    (net (code "88") (name "TIM12_EX2_2") (class "Default")
      (node (ref "JP5") (pin "4") (pinfunction "4_4") (pintype "passive"))
      (node (ref "U$1") (pin "76") (pinfunction "PB15_76") (pintype "bidirectional"))
    )
    (net (code "89") (name "UART4_WIFI_RX") (class "Default")
      (node (ref "U$1") (pin "112") (pinfunction "PC11_112") (pintype "bidirectional"))
    )
    (net (code "90") (name "UART4_WIFI_TX") (class "Default")
      (node (ref "U$1") (pin "111") (pinfunction "PC10_111") (pintype "bidirectional"))
    )
    (net (code "91") (name "USB_DM") (class "Default")
      (node (ref "U$1") (pin "103") (pinfunction "PA11_103") (pintype "bidirectional"))
    )
    (net (code "92") (name "USB_DP") (class "Default")
      (node (ref "U$1") (pin "104") (pinfunction "PA12_104") (pintype "bidirectional"))
    )
    (net (code "93") (name "unconnected-(JP4-Pad1)") (class "Default")
      (node (ref "JP4") (pin "1") (pinfunction "1_1") (pintype "passive"))
    )
    (net (code "94") (name "unconnected-(JP4-Pad2)") (class "Default")
      (node (ref "JP4") (pin "2") (pinfunction "2_2") (pintype "passive"))
    )
    (net (code "95") (name "unconnected-(JP5-Pad2)") (class "Default")
      (node (ref "JP5") (pin "2") (pinfunction "2_2") (pintype "passive"))
    )
    (net (code "96") (name "unconnected-(JP6-Pad2)") (class "Default")
      (node (ref "JP6") (pin "2") (pinfunction "2_2") (pintype "passive"))
    )
    (net (code "97") (name "unconnected-(U$1-PA10-Pad102)") (class "Default")
      (node (ref "U$1") (pin "102") (pinfunction "PA10_102") (pintype "bidirectional"))
    )
    (net (code "98") (name "unconnected-(U$1-PA15-Pad110)") (class "Default")
      (node (ref "U$1") (pin "110") (pinfunction "PA15_110") (pintype "bidirectional"))
    )
    (net (code "99") (name "unconnected-(U$1-PB2-Pad48)") (class "Default")
      (node (ref "U$1") (pin "48") (pinfunction "PB2_48") (pintype "bidirectional"))
    )
    (net (code "100") (name "unconnected-(U$1-PB4-Pad134)") (class "Default")
      (node (ref "U$1") (pin "134") (pinfunction "PB4_134") (pintype "bidirectional"))
    )
    (net (code "101") (name "unconnected-(U$1-PB5-Pad135)") (class "Default")
      (node (ref "U$1") (pin "135") (pinfunction "PB5_135") (pintype "bidirectional"))
    )
    (net (code "102") (name "unconnected-(U$1-PB8-Pad139)") (class "Default")
      (node (ref "U$1") (pin "139") (pinfunction "PB8_139") (pintype "bidirectional"))
    )
    (net (code "103") (name "unconnected-(U$1-PB9-Pad140)") (class "Default")
      (node (ref "U$1") (pin "140") (pinfunction "PB9_140") (pintype "bidirectional"))
    )
    (net (code "104") (name "unconnected-(U$1-PB12-Pad73)") (class "Default")
      (node (ref "U$1") (pin "73") (pinfunction "PB12_73") (pintype "bidirectional"))
    )
    (net (code "105") (name "unconnected-(U$1-PB13-Pad74)") (class "Default")
      (node (ref "U$1") (pin "74") (pinfunction "PB13_74") (pintype "bidirectional"))
    )
    (net (code "106") (name "unconnected-(U$1-PC12-Pad113)") (class "Default")
      (node (ref "U$1") (pin "113") (pinfunction "PC12_113") (pintype "bidirectional"))
    )
    (net (code "107") (name "unconnected-(U$1-PD0-Pad114)") (class "Default")
      (node (ref "U$1") (pin "114") (pinfunction "PD0_114") (pintype "bidirectional"))
    )
    (net (code "108") (name "unconnected-(U$1-PD1-Pad115)") (class "Default")
      (node (ref "U$1") (pin "115") (pinfunction "PD1_115") (pintype "bidirectional"))
    )
    (net (code "109") (name "unconnected-(U$1-PD2-Pad116)") (class "Default")
      (node (ref "U$1") (pin "116") (pinfunction "PD2_116") (pintype "bidirectional"))
    )
    (net (code "110") (name "unconnected-(U$1-PD3-Pad117)") (class "Default")
      (node (ref "U$1") (pin "117") (pinfunction "PD3_117") (pintype "bidirectional"))
    )
    (net (code "111") (name "unconnected-(U$1-PD7-Pad123)") (class "Default")
      (node (ref "U$1") (pin "123") (pinfunction "PD7_123") (pintype "bidirectional"))
    )
    (net (code "112") (name "unconnected-(U$1-PD8-Pad77)") (class "Default")
      (node (ref "U$1") (pin "77") (pinfunction "PD8_77") (pintype "bidirectional"))
    )
    (net (code "113") (name "unconnected-(U$1-PD9-Pad78)") (class "Default")
      (node (ref "U$1") (pin "78") (pinfunction "PD9_78") (pintype "bidirectional"))
    )
    (net (code "114") (name "unconnected-(U$1-PD10-Pad79)") (class "Default")
      (node (ref "U$1") (pin "79") (pinfunction "PD10_79") (pintype "bidirectional"))
    )
    (net (code "115") (name "unconnected-(U$1-PD11-Pad80)") (class "Default")
      (node (ref "U$1") (pin "80") (pinfunction "PD11_80") (pintype "bidirectional"))
    )
    (net (code "116") (name "unconnected-(U$1-PE0-Pad141)") (class "Default")
      (node (ref "U$1") (pin "141") (pinfunction "PE0_141") (pintype "bidirectional"))
    )
    (net (code "117") (name "unconnected-(U$1-PE1-Pad142)") (class "Default")
      (node (ref "U$1") (pin "142") (pinfunction "PE1_142") (pintype "bidirectional"))
    )
    (net (code "118") (name "unconnected-(U$1-PE2-Pad1)") (class "Default")
      (node (ref "U$1") (pin "1") (pinfunction "PE2_1") (pintype "bidirectional"))
    )
    (net (code "119") (name "unconnected-(U$1-PE3-Pad2)") (class "Default")
      (node (ref "U$1") (pin "2") (pinfunction "PE3_2") (pintype "bidirectional"))
    )
    (net (code "120") (name "unconnected-(U$1-PE4-Pad3)") (class "Default")
      (node (ref "U$1") (pin "3") (pinfunction "PE4_3") (pintype "bidirectional"))
    )
    (net (code "121") (name "unconnected-(U$1-PF12-Pad50)") (class "Default")
      (node (ref "U$1") (pin "50") (pinfunction "PF12_50") (pintype "bidirectional"))
    )
    (net (code "122") (name "unconnected-(U$1-PF13-Pad53)") (class "Default")
      (node (ref "U$1") (pin "53") (pinfunction "PF13_53") (pintype "bidirectional"))
    )
    (net (code "123") (name "unconnected-(U$1-PG3-Pad88)") (class "Default")
      (node (ref "U$1") (pin "88") (pinfunction "PG3_88") (pintype "bidirectional"))
    )
    (net (code "124") (name "unconnected-(U$1-PG4-Pad89)") (class "Default")
      (node (ref "U$1") (pin "89") (pinfunction "PG4_89") (pintype "bidirectional"))
    )
    (net (code "125") (name "unconnected-(U$1-PG5-Pad90)") (class "Default")
      (node (ref "U$1") (pin "90") (pinfunction "PG5_90") (pintype "bidirectional"))
    )
    (net (code "126") (name "unconnected-(U$1-PG6-Pad91)") (class "Default")
      (node (ref "U$1") (pin "91") (pinfunction "PG6_91") (pintype "bidirectional"))
    )
    (net (code "127") (name "unconnected-(U$1-PG7-Pad92)") (class "Default")
      (node (ref "U$1") (pin "92") (pinfunction "PG7_92") (pintype "bidirectional"))
    )
    (net (code "128") (name "unconnected-(U$1-PG8-Pad93)") (class "Default")
      (node (ref "U$1") (pin "93") (pinfunction "PG8_93") (pintype "bidirectional"))
    )
    (net (code "129") (name "unconnected-(U$1-PG13-Pad128)") (class "Default")
      (node (ref "U$1") (pin "128") (pinfunction "PG13_128") (pintype "bidirectional"))
    )
    (net (code "130") (name "unconnected-(U$1-PG14-Pad129)") (class "Default")
      (node (ref "U$1") (pin "129") (pinfunction "PG14_129") (pintype "bidirectional"))
    )
    (net (code "131") (name "unconnected-(U$1-PG15-Pad132)") (class "Default")
      (node (ref "U$1") (pin "132") (pinfunction "PG15_132") (pintype "bidirectional"))
    )
    (net (code "132") (name "unconnected-(X2-Pad1)") (class "Default")
      (node (ref "X2") (pin "1") (pinfunction "1_1") (pintype "passive"))
    )
    (net (code "133") (name "unconnected-(X2-Pad2)") (class "Default")
      (node (ref "X2") (pin "2") (pinfunction "2_2") (pintype "passive"))
    )
    (net (code "134") (name "unconnected-(X2-Pad3)") (class "Default")
      (node (ref "X2") (pin "3") (pinfunction "3_3") (pintype "passive"))
    )
    (net (code "135") (name "unconnected-(X2-Pad4)") (class "Default")
      (node (ref "X2") (pin "4") (pinfunction "4_4") (pintype "passive"))
    )
  )
)
